# Electrical_Diagram.net
KiCad netlist of a schematic drawn in EAGLE
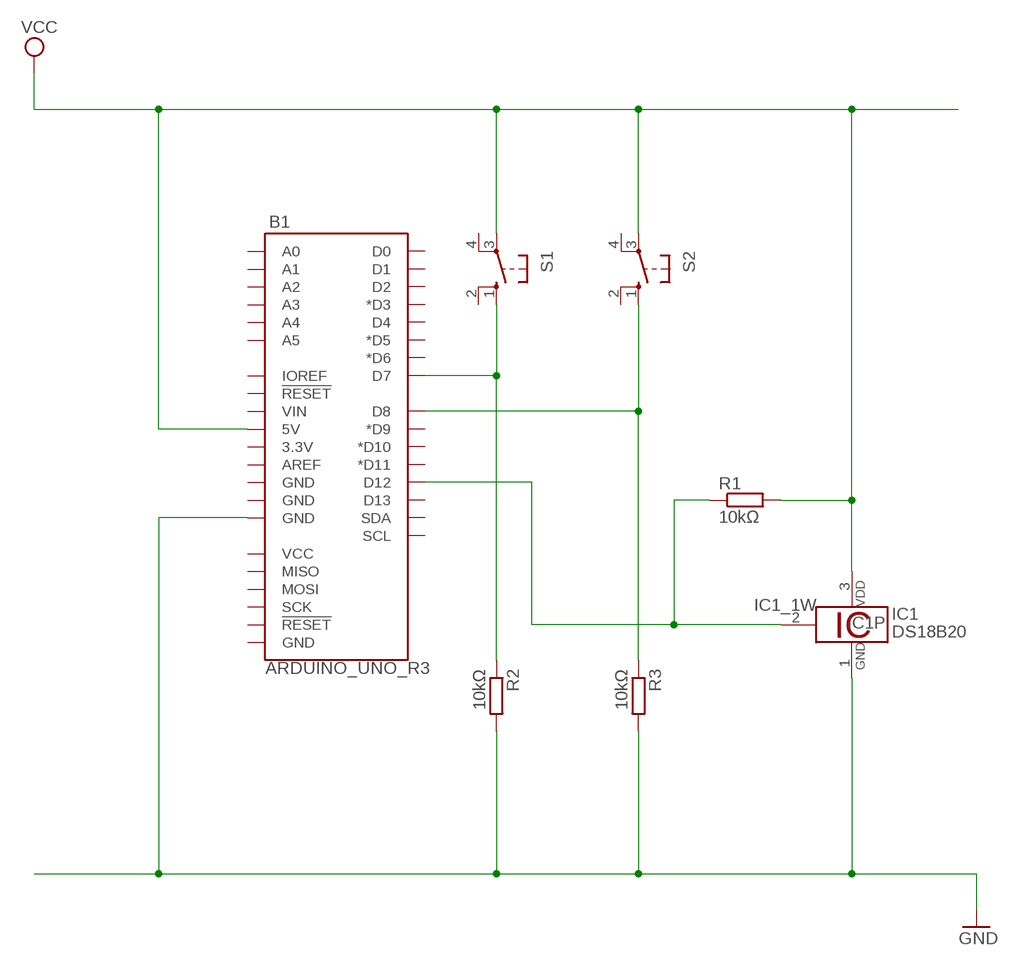
[diagram p0: schematic, sheet 1]

(export (version "E")
  (design (tool "Eeschema 10.0.6"))
  (components
    (comp (ref "B1")
      (value "ARDUINO_UNO_R3")
      (footprint "eagle-import:ARDUINO_R3")
      (libsource (lib "eagle-import") (part "ARDUINO_UNO_R3"))
    )
    (comp (ref "IC1")
      (value "DS18B20")
      (footprint "eagle-import:TO92-")
      (libsource (lib "eagle-import") (part "DS18B20"))
    )
    (comp (ref "R1")
      (value "10kΩ")
      (footprint "eagle-import:0207_12")
      (libsource (lib "eagle-import") (part "R-EU_0207/12"))
    )
    (comp (ref "R2")
      (value "10kΩ")
      (footprint "eagle-import:0207_12")
      (libsource (lib "eagle-import") (part "R-EU_0207/12"))
    )
    (comp (ref "R3")
      (value "10kΩ")
      (footprint "eagle-import:0207_12")
      (libsource (lib "eagle-import") (part "R-EU_0207/12"))
    )
    (comp (ref "S1")
      (value "10-XX")
      (footprint "eagle-import:B3F-10XX")
      (fields (field (name "MPN") "B3F-1000"))
      (libsource (lib "eagle-import") (part "10-XX"))
    )
    (comp (ref "S2")
      (value "10-XX")
      (footprint "eagle-import:B3F-10XX")
      (fields (field (name "MPN") "B3F-1000"))
      (libsource (lib "eagle-import") (part "10-XX"))
    )
  )
  (nets
    (net (code "1") (name "GND") (class "Default")
      (node (ref "B1") (pin "GND@2") (pinfunction "GND_GND@2") (pintype "bidirectional"))
      (node (ref "IC1") (pin "1") (pinfunction "GND_1") (pintype "power_in"))
      (node (ref "R2") (pin "2") (pinfunction "2_2") (pintype "passive"))
      (node (ref "R3") (pin "2") (pinfunction "2_2") (pintype "passive"))
    )
    (net (code "2") (name "Net-(IC1C-1W)") (class "Default")
      (node (ref "B1") (pin "D12") (pinfunction "D12_D12") (pintype "bidirectional"))
      (node (ref "IC1") (pin "2") (pinfunction "1W_2") (pintype "power_in"))
      (node (ref "R1") (pin "1") (pinfunction "1_1") (pintype "passive"))
    )
    (net (code "3") (name "Net-(S1-S)") (class "Default")
      (node (ref "B1") (pin "D7") (pinfunction "D7_D7") (pintype "bidirectional"))
      (node (ref "R2") (pin "1") (pinfunction "1_1") (pintype "passive"))
      (node (ref "S1") (pin "1") (pinfunction "S_1") (pintype "passive"))
    )
    (net (code "4") (name "Net-(S2-S)") (class "Default")
      (node (ref "B1") (pin "D8") (pinfunction "D8_D8") (pintype "bidirectional"))
      (node (ref "R3") (pin "1") (pinfunction "1_1") (pintype "passive"))
      (node (ref "S2") (pin "1") (pinfunction "S_1") (pintype "passive"))
    )
    (net (code "5") (name "VCC") (class "Default")
      (node (ref "B1") (pin "5V") (pinfunction "5V_5V") (pintype "bidirectional"))
      (node (ref "IC1") (pin "3") (pinfunction "VDD_3") (pintype "power_in"))
      (node (ref "R1") (pin "2") (pinfunction "2_2") (pintype "passive"))
      (node (ref "S1") (pin "3") (pinfunction "P_3") (pintype "passive"))
      (node (ref "S2") (pin "3") (pinfunction "P_3") (pintype "passive"))
    )
    (net (code "6") (name "unconnected-(B1-*D3-PadD3)") (class "Default")
      (node (ref "B1") (pin "D3") (pinfunction "*D3_D3") (pintype "bidirectional"))
    )
    (net (code "7") (name "unconnected-(B1-*D5-PadD5)") (class "Default")
      (node (ref "B1") (pin "D5") (pinfunction "*D5_D5") (pintype "bidirectional"))
    )
    (net (code "8") (name "unconnected-(B1-*D6-PadD6)") (class "Default")
      (node (ref "B1") (pin "D6") (pinfunction "*D6_D6") (pintype "bidirectional"))
    )
    (net (code "9") (name "unconnected-(B1-*D9-PadD9)") (class "Default")
      (node (ref "B1") (pin "D9") (pinfunction "*D9_D9") (pintype "bidirectional"))
    )
    (net (code "10") (name "unconnected-(B1-*D10-PadD10)") (class "Default")
      (node (ref "B1") (pin "D10") (pinfunction "*D10_D10") (pintype "bidirectional"))
    )
    (net (code "11") (name "unconnected-(B1-*D11-PadD11)") (class "Default")
      (node (ref "B1") (pin "D11") (pinfunction "*D11_D11") (pintype "bidirectional"))
    )
    (net (code "12") (name "unconnected-(B1-GND-PadGND@1)") (class "Default")
      (node (ref "B1") (pin "GND@1") (pinfunction "GND_GND@1") (pintype "bidirectional"))
    )
    (net (code "13") (name "unconnected-(B1-GND-PadGND@3)") (class "Default")
      (node (ref "B1") (pin "GND@3") (pinfunction "GND_GND@3") (pintype "bidirectional"))
    )
    (net (code "14") (name "unconnected-(B1-GND-PadGND@4)") (class "Default")
      (node (ref "B1") (pin "GND@4") (pinfunction "GND_GND@4") (pintype "bidirectional"))
    )
    (net (code "15") (name "unconnected-(B1-Pad3.3V)") (class "Default")
      (node (ref "B1") (pin "3.3V") (pinfunction "3.3V_3.3V") (pintype "bidirectional"))
    )
    (net (code "16") (name "unconnected-(B1-PadA0)") (class "Default")
      (node (ref "B1") (pin "A0") (pinfunction "A0_A0") (pintype "bidirectional"))
    )
    (net (code "17") (name "unconnected-(B1-PadA1)") (class "Default")
      (node (ref "B1") (pin "A1") (pinfunction "A1_A1") (pintype "bidirectional"))
    )
    (net (code "18") (name "unconnected-(B1-PadA2)") (class "Default")
      (node (ref "B1") (pin "A2") (pinfunction "A2_A2") (pintype "bidirectional"))
    )
    (net (code "19") (name "unconnected-(B1-PadA3)") (class "Default")
      (node (ref "B1") (pin "A3") (pinfunction "A3_A3") (pintype "bidirectional"))
    )
    (net (code "20") (name "unconnected-(B1-PadA4)") (class "Default")
      (node (ref "B1") (pin "A4") (pinfunction "A4_A4") (pintype "bidirectional"))
    )
    (net (code "21") (name "unconnected-(B1-PadA5)") (class "Default")
      (node (ref "B1") (pin "A5") (pinfunction "A5_A5") (pintype "bidirectional"))
    )
    (net (code "22") (name "unconnected-(B1-PadAREF)") (class "Default")
      (node (ref "B1") (pin "AREF") (pinfunction "AREF_AREF") (pintype "bidirectional"))
    )
    (net (code "23") (name "unconnected-(B1-PadD0)") (class "Default")
      (node (ref "B1") (pin "D0") (pinfunction "D0_D0") (pintype "bidirectional"))
    )
    (net (code "24") (name "unconnected-(B1-PadD1)") (class "Default")
      (node (ref "B1") (pin "D1") (pinfunction "D1_D1") (pintype "bidirectional"))
    )
    (net (code "25") (name "unconnected-(B1-PadD2)") (class "Default")
      (node (ref "B1") (pin "D2") (pinfunction "D2_D2") (pintype "bidirectional"))
    )
    (net (code "26") (name "unconnected-(B1-PadD4)") (class "Default")
      (node (ref "B1") (pin "D4") (pinfunction "D4_D4") (pintype "bidirectional"))
    )
    (net (code "27") (name "unconnected-(B1-PadD13)") (class "Default")
      (node (ref "B1") (pin "D13") (pinfunction "D13_D13") (pintype "bidirectional"))
    )
    (net (code "28") (name "unconnected-(B1-PadIOREF)") (class "Default")
      (node (ref "B1") (pin "IOREF") (pinfunction "IOREF_IOREF") (pintype "bidirectional"))
    )
    (net (code "29") (name "unconnected-(B1-PadMISO)") (class "Default")
      (node (ref "B1") (pin "MISO") (pinfunction "MISO_MISO") (pintype "bidirectional"))
    )
    (net (code "30") (name "unconnected-(B1-PadMOSI)") (class "Default")
      (node (ref "B1") (pin "MOSI") (pinfunction "MOSI_MOSI") (pintype "bidirectional"))
    )
    (net (code "31") (name "unconnected-(B1-PadSCK)") (class "Default")
      (node (ref "B1") (pin "SCK") (pinfunction "SCK_SCK") (pintype "bidirectional"))
    )
    (net (code "32") (name "unconnected-(B1-PadSCL)") (class "Default")
      (node (ref "B1") (pin "SCL") (pinfunction "SCL_SCL") (pintype "bidirectional"))
    )
    (net (code "33") (name "unconnected-(B1-PadSDA)") (class "Default")
      (node (ref "B1") (pin "SDA") (pinfunction "SDA_SDA") (pintype "bidirectional"))
    )
    (net (code "34") (name "unconnected-(B1-PadVCC)") (class "Default")
      (node (ref "B1") (pin "VCC") (pinfunction "VCC_VCC") (pintype "bidirectional"))
    )
    (net (code "35") (name "unconnected-(B1-PadVIN)") (class "Default")
      (node (ref "B1") (pin "VIN") (pinfunction "VIN_VIN") (pintype "bidirectional"))
    )
    (net (code "36") (name "unconnected-(B1-~{RESET}-PadRESET@1)") (class "Default")
      (node (ref "B1") (pin "RESET@1") (pinfunction "~{RESET}_RESET@1") (pintype "bidirectional"))
    )
    (net (code "37") (name "unconnected-(B1-~{RESET}-PadRESET@2)") (class "Default")
      (node (ref "B1") (pin "RESET@2") (pinfunction "~{RESET}_RESET@2") (pintype "bidirectional"))
    )
    (net (code "38") (name "unconnected-(S1-P1-Pad4)") (class "Default")
      (node (ref "S1") (pin "4") (pinfunction "P1_4") (pintype "passive"))
    )
    (net (code "39") (name "unconnected-(S1-S1-Pad2)") (class "Default")
      (node (ref "S1") (pin "2") (pinfunction "S1_2") (pintype "passive"))
    )
    (net (code "40") (name "unconnected-(S2-P1-Pad4)") (class "Default")
      (node (ref "S2") (pin "4") (pinfunction "P1_4") (pintype "passive"))
    )
    (net (code "41") (name "unconnected-(S2-S1-Pad2)") (class "Default")
      (node (ref "S2") (pin "2") (pinfunction "S1_2") (pintype "passive"))
    )
  )
)
